# Pixel1_0_2.net
KiCad netlist of a schematic drawn in Altium Designer
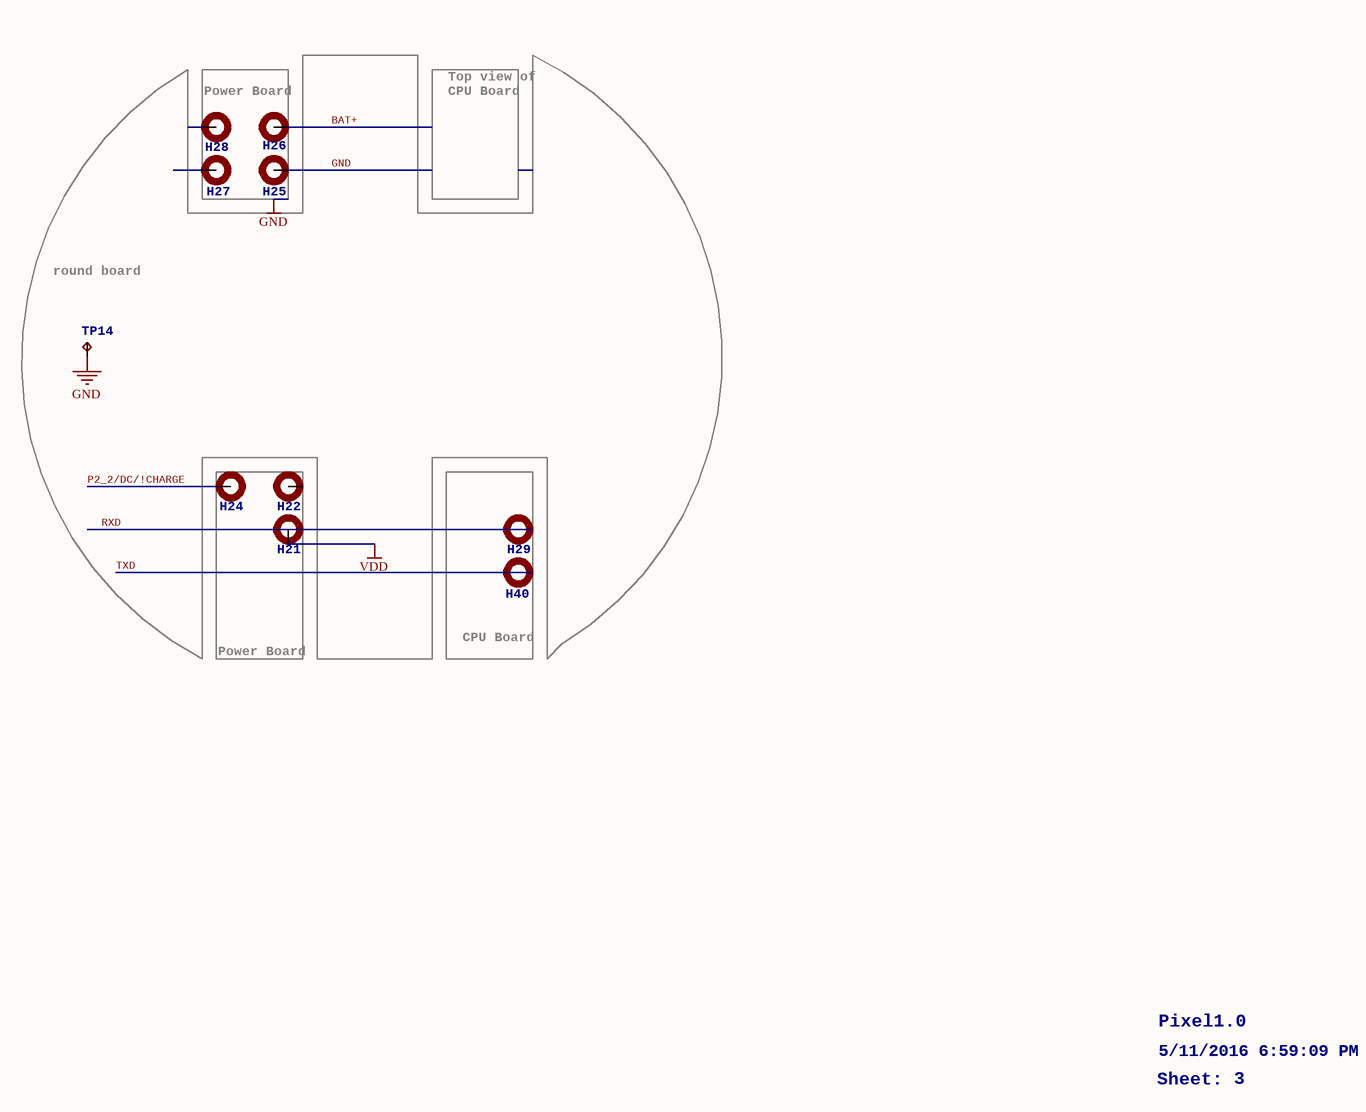
[diagram p0: Pixel1.0_2.SchDoc]

(export (version "E")
  (design (tool "Eeschema 10.0.6"))
  (components
    (comp (ref "H21")
      (value "MOUNT-PAD-ROUNDTMOUNT1")
      (footprint "T-MOUNT1")
      (description "MOUNTING PAD, round")
      (libsource (lib "Pixel1.0") (part "MOUNT-PAD-ROUNDTMOUNT1"))
    )
    (comp (ref "H22")
      (value "MOUNT-PAD-ROUNDTMOUNT1")
      (footprint "T-MOUNT1")
      (description "MOUNTING PAD, round")
      (libsource (lib "Pixel1.0") (part "MOUNT-PAD-ROUNDTMOUNT1"))
    )
    (comp (ref "H24")
      (value "MOUNT-PAD-ROUNDTMOUNT1")
      (footprint "T-MOUNT1")
      (description "MOUNTING PAD, round")
      (libsource (lib "Pixel1.0") (part "MOUNT-PAD-ROUNDTMOUNT1"))
    )
    (comp (ref "H25")
      (value "MOUNT-PAD-ROUNDTMOUNT1")
      (footprint "T-MOUNT1")
      (description "MOUNTING PAD, round")
      (libsource (lib "Pixel1.0") (part "MOUNT-PAD-ROUNDTMOUNT1"))
    )
    (comp (ref "H26")
      (value "MOUNT-PAD-ROUNDTMOUNT1")
      (footprint "T-MOUNT1")
      (description "MOUNTING PAD, round")
      (libsource (lib "Pixel1.0") (part "MOUNT-PAD-ROUNDTMOUNT1"))
    )
    (comp (ref "H27")
      (value "MOUNT-PAD-ROUNDTMOUNT1")
      (footprint "T-MOUNT1")
      (description "MOUNTING PAD, round")
      (libsource (lib "Pixel1.0") (part "MOUNT-PAD-ROUNDTMOUNT1"))
    )
    (comp (ref "H28")
      (value "MOUNT-PAD-ROUNDTMOUNT1")
      (footprint "T-MOUNT1")
      (description "MOUNTING PAD, round")
      (libsource (lib "Pixel1.0") (part "MOUNT-PAD-ROUNDTMOUNT1"))
    )
    (comp (ref "H29")
      (value "MOUNT-PAD-ROUND1.5MMX1MM")
      (footprint "TMOUNT4")
      (description "MOUNTING PAD, round")
      (libsource (lib "Pixel1.0") (part "MOUNT-PAD-ROUND1.5MMX1MM"))
    )
    (comp (ref "H40")
      (value "MOUNT-PAD-ROUND1.5MMX1MM")
      (footprint "TMOUNT4")
      (description "MOUNTING PAD, round")
      (libsource (lib "Pixel1.0") (part "MOUNT-PAD-ROUND1.5MMX1MM"))
    )
    (comp (ref "TP14")
      (value "TPTP06R")
      (footprint "TP06R")
      (description "Test pad")
      (libsource (lib "testpad") (part "TPTP06R"))
    )
  )
  (nets
    (net (code "1") (name "/BAT+") (class "Default")
      (node (ref "H26") (pin "1") (pinfunction "MOUNT_1") (pintype "passive"))
    )
    (net (code "2") (name "/P2_2{slash}DC{slash}!CHARGE") (class "Default")
      (node (ref "H24") (pin "1") (pinfunction "MOUNT_1") (pintype "passive"))
    )
    (net (code "3") (name "/RXD") (class "Default")
      (node (ref "H29") (pin "1") (pinfunction "MOUNT_1") (pintype "passive"))
    )
    (net (code "4") (name "/TXD") (class "Default")
      (node (ref "H40") (pin "1") (pinfunction "MOUNT_1") (pintype "passive"))
    )
    (net (code "5") (name "GND") (class "Default")
      (node (ref "H25") (pin "1") (pinfunction "MOUNT_1") (pintype "passive"))
      (node (ref "TP14") (pin "TP") (pinfunction "TP_TP") (pintype "passive"))
    )
    (net (code "6") (name "VDD") (class "Default")
      (node (ref "H21") (pin "1") (pinfunction "MOUNT_1") (pintype "passive"))
    )
    (net (code "7") (name "unconnected-(H22-MOUNT-Pad1)") (class "Default")
      (node (ref "H22") (pin "1") (pinfunction "MOUNT_1") (pintype "passive"))
    )
    (net (code "8") (name "unconnected-(H27-MOUNT-Pad1)") (class "Default")
      (node (ref "H27") (pin "1") (pinfunction "MOUNT_1") (pintype "passive"))
    )
    (net (code "9") (name "unconnected-(H28-MOUNT-Pad1)") (class "Default")
      (node (ref "H28") (pin "1") (pinfunction "MOUNT_1") (pintype "passive"))
    )
  )
)
